# Audio_Amplifier.net
KiCad netlist of a schematic drawn in EAGLE
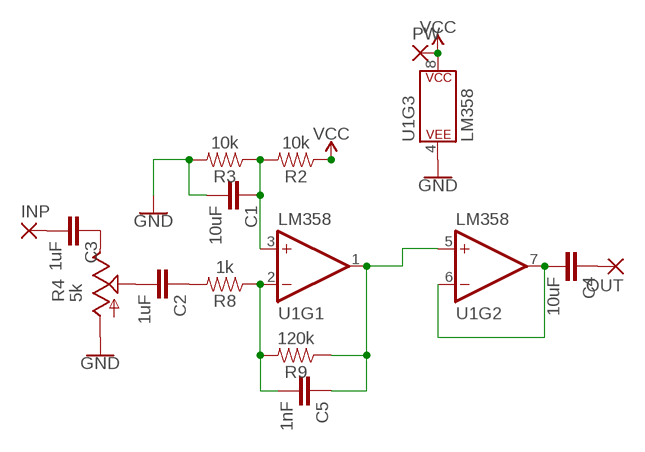
[diagram p0: schematic, sheet 1]

(export (version "E")
  (design (tool "Eeschema 10.0.6"))
  (components
    (comp (ref "C1")
      (value "10uF")
      (footprint "eagle-import:C5B3.5")
      (libsource (lib "eagle-import") (part "C5/3.5"))
    )
    (comp (ref "C2")
      (value "1uF")
      (footprint "eagle-import:C5B3.5")
      (libsource (lib "eagle-import") (part "C5/3.5"))
    )
    (comp (ref "C3")
      (value "1uF")
      (footprint "eagle-import:C5B3.5")
      (libsource (lib "eagle-import") (part "C5/3.5"))
    )
    (comp (ref "C4")
      (value "10uF")
      (footprint "eagle-import:C5B3.5")
      (libsource (lib "eagle-import") (part "C5/3.5"))
    )
    (comp (ref "C5")
      (value "1nF")
      (footprint "eagle-import:C5B3.5")
      (libsource (lib "eagle-import") (part "C5/3.5"))
    )
    (comp (ref "INP")
      (value "2,54/1,1")
      (footprint "eagle-import:2,54_1,1")
      (libsource (lib "eagle-import") (part "2,54/1,1"))
    )
    (comp (ref "OUT")
      (value "2,54/1,1")
      (footprint "eagle-import:2,54_1,1")
      (libsource (lib "eagle-import") (part "2,54/1,1"))
    )
    (comp (ref "PW")
      (value "2,54/1,1")
      (footprint "eagle-import:2,54_1,1")
      (libsource (lib "eagle-import") (part "2,54/1,1"))
    )
    (comp (ref "R2")
      (value "10k")
      (footprint "eagle-import:AXIAL-0.3")
      (libsource (lib "eagle-import") (part "1KOHM-HORIZ-1/4W-1%"))
    )
    (comp (ref "R3")
      (value "10k")
      (footprint "eagle-import:AXIAL-0.3")
      (libsource (lib "eagle-import") (part "1KOHM-HORIZ-1/4W-1%"))
    )
    (comp (ref "R4")
      (value "5k")
      (footprint "eagle-import:B25V")
      (libsource (lib "eagle-import") (part "TRIM_US-B25V"))
    )
    (comp (ref "R8")
      (value "1k")
      (footprint "eagle-import:AXIAL-0.3")
      (libsource (lib "eagle-import") (part "1KOHM-HORIZ-1/4W-1%"))
    )
    (comp (ref "R9")
      (value "120k")
      (footprint "eagle-import:AXIAL-0.3")
      (libsource (lib "eagle-import") (part "1KOHM-HORIZ-1/4W-1%"))
    )
    (comp (ref "U1")
      (value "LM358")
      (footprint "eagle-import:DIP08")
      (libsource (lib "eagle-import") (part "LM358"))
    )
  )
  (nets
    (net (code "1") (name "GND") (class "Default")
      (node (ref "C1") (pin "2") (pinfunction "2_2") (pintype "passive"))
      (node (ref "R3") (pin "P$2") (pinfunction "2_P$2") (pintype "passive"))
      (node (ref "R4") (pin "A") (pinfunction "A_A") (pintype "passive"))
      (node (ref "U1") (pin "4") (pinfunction "P$V-_4") (pintype "bidirectional"))
    )
    (net (code "2") (name "Net-(C2-Pad2)") (class "Default")
      (node (ref "C2") (pin "2") (pinfunction "2_2") (pintype "passive"))
      (node (ref "R4") (pin "S") (pinfunction "S_S") (pintype "passive"))
    )
    (net (code "3") (name "Net-(C3-Pad1)") (class "Default")
      (node (ref "C3") (pin "1") (pinfunction "1_1") (pintype "passive"))
      (node (ref "R4") (pin "E") (pinfunction "E_E") (pintype "passive"))
    )
    (net (code "4") (name "Net-(INP-P)") (class "Default")
      (node (ref "C3") (pin "2") (pinfunction "2_2") (pintype "passive"))
      (node (ref "INP") (pin "1") (pinfunction "P_1") (pintype "passive"))
    )
    (net (code "5") (name "Net-(OUT-P)") (class "Default")
      (node (ref "C4") (pin "1") (pinfunction "1_1") (pintype "passive"))
      (node (ref "OUT") (pin "1") (pinfunction "P_1") (pintype "passive"))
    )
    (net (code "6") (name "Net-(R2-2)") (class "Default")
      (node (ref "C1") (pin "1") (pinfunction "1_1") (pintype "passive"))
      (node (ref "R2") (pin "P$2") (pinfunction "2_P$2") (pintype "passive"))
      (node (ref "R3") (pin "P$1") (pinfunction "1_P$1") (pintype "passive"))
      (node (ref "U1") (pin "3") (pinfunction "+IN_3") (pintype "input"))
    )
    (net (code "7") (name "Net-(R8-1)") (class "Default")
      (node (ref "C5") (pin "2") (pinfunction "2_2") (pintype "passive"))
      (node (ref "R8") (pin "P$1") (pinfunction "1_P$1") (pintype "passive"))
      (node (ref "R9") (pin "P$2") (pinfunction "2_P$2") (pintype "passive"))
      (node (ref "U1") (pin "2") (pinfunction "-IN_2") (pintype "input"))
    )
    (net (code "8") (name "Net-(R8-2)") (class "Default")
      (node (ref "C2") (pin "1") (pinfunction "1_1") (pintype "passive"))
      (node (ref "R8") (pin "P$2") (pinfunction "2_P$2") (pintype "passive"))
    )
    (net (code "9") (name "Net-(R9-1)") (class "Default")
      (node (ref "C5") (pin "1") (pinfunction "1_1") (pintype "passive"))
      (node (ref "R9") (pin "P$1") (pinfunction "1_P$1") (pintype "passive"))
      (node (ref "U1") (pin "1") (pinfunction "OUT_1") (pintype "output"))
      (node (ref "U1") (pin "5") (pinfunction "+IN_5") (pintype "input"))
    )
    (net (code "10") (name "Net-(U1B--IN)") (class "Default")
      (node (ref "C4") (pin "2") (pinfunction "2_2") (pintype "passive"))
      (node (ref "U1") (pin "6") (pinfunction "-IN_6") (pintype "input"))
      (node (ref "U1") (pin "7") (pinfunction "OUT_7") (pintype "output"))
    )
    (net (code "11") (name "VCC") (class "Default")
      (node (ref "PW") (pin "1") (pinfunction "P_1") (pintype "passive"))
      (node (ref "R2") (pin "P$1") (pinfunction "1_P$1") (pintype "passive"))
      (node (ref "U1") (pin "8") (pinfunction "P$V+_8") (pintype "bidirectional"))
    )
  )
)
